# USB_Type_C.net
KiCad netlist of a schematic drawn in Altium Designer
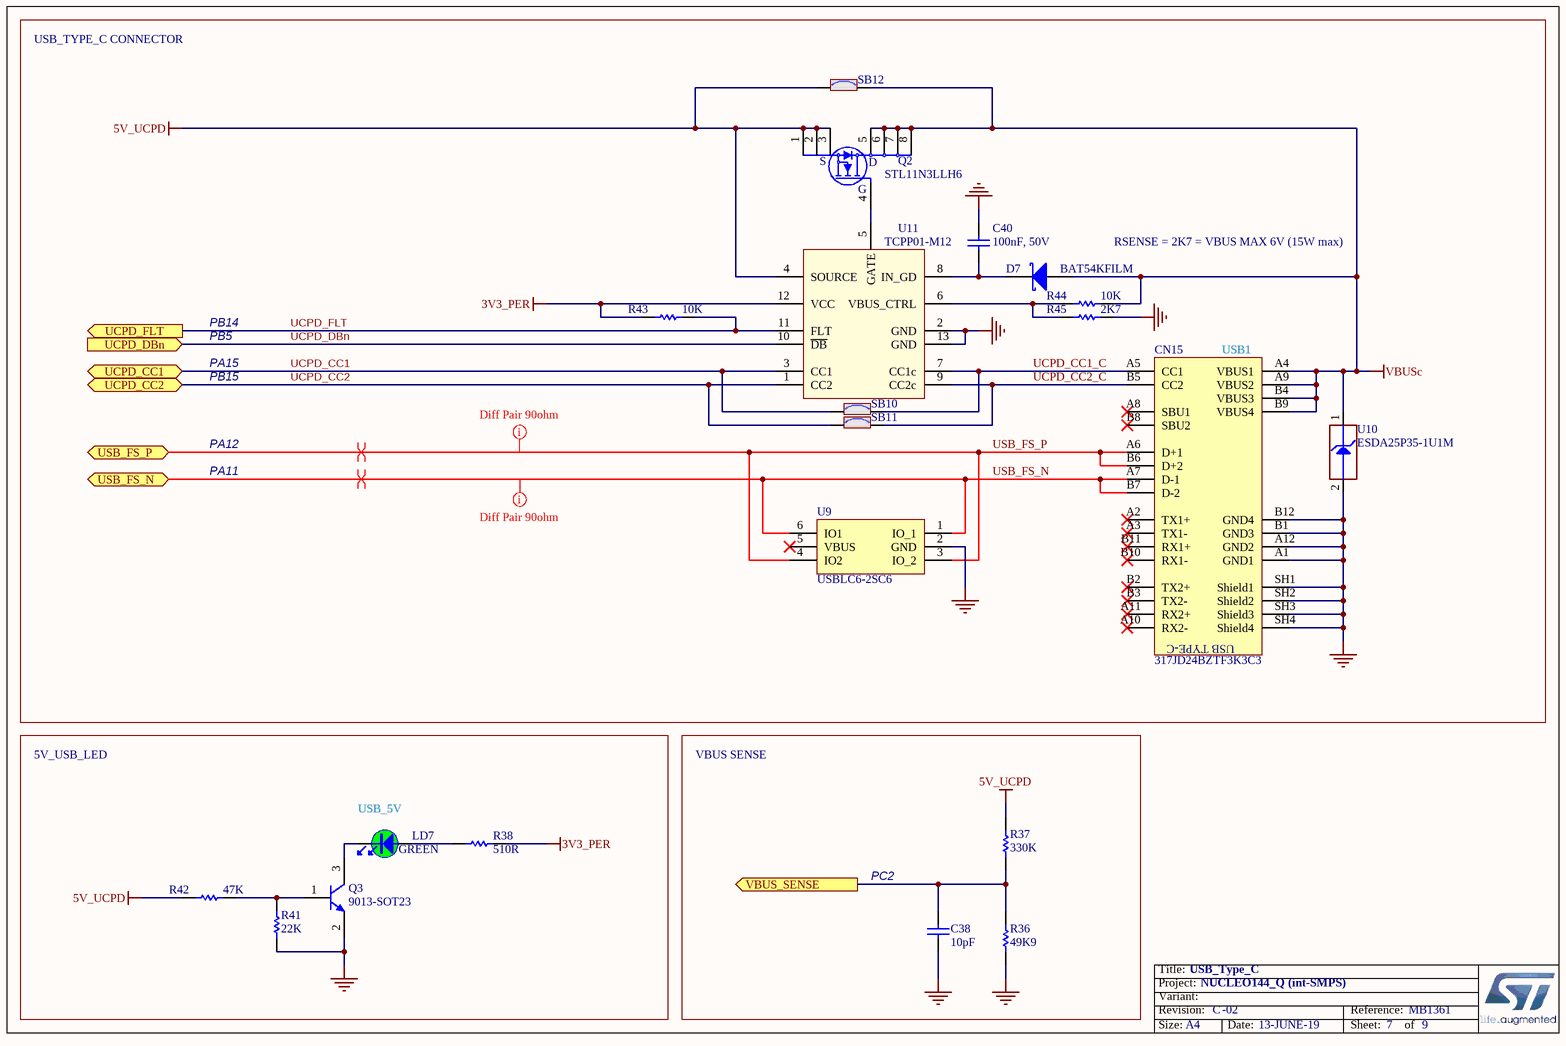
[diagram p0: USB_Type_C.SchDoc]

(export (version "E")
  (design (tool "Eeschema 10.0.6"))
  (components
    (comp (ref "C38")
      (value "10pF")
      (footprint "C0603")
      (description "Capacitor, MLCC, 10pF, 50V, NPO, 5%, 0603, T=0,8mm")
      (fields
        (field (name "INTERNAL_PART_NUMBER") "MCD-00637")
        (field (name "MANUFACTURER_PART_NUMBER") "CC0603JRNPO9BN100")
        (field (name "PROVIDED_BY") "subcon")
      )
      (libsource (lib "MCD_PARTS_database") (part "Capacitor"))
    )
    (comp (ref "C40")
      (value "100nF, 50V")
      (footprint "C0603")
      (description "Capacitor,100nF,50V,X7R,10%,0603")
      (fields
        (field (name "INTERNAL_PART_NUMBER") "MCD-01099")
        (field (name "MANUFACTURER_PART_NUMBER") "CC0603KRX7R9BB104")
        (field (name "PROVIDED_BY") "SUBCO")
      )
      (libsource (lib "MCD_PARTS_database") (part "Capacitor"))
    )
    (comp (ref "CN15")
      (value "317JD24BZTF3K3C3")
      (footprint "CON_USB-TYPEC_COXOC_317JD24BZTF3K3C3")
      (description "USB tyce C certified receptacle for 1.6mm pcb height")
      (fields
        (field (name "INTERNAL_PART_NUMBER") "MCD-01108")
        (field (name "MANUFACTURER") "CHANT SINCERE (COXOC)")
        (field (name "PROVIDED_BY") "SUBCO")
      )
      (libsource (lib "MCD_PARTS_database") (part "USB_TYPE_C_Receptacle_317JD24BZTF3K3C3"))
    )
    (comp (ref "D7")
      (value "BAT54KFILM")
      (footprint "DIO_SOD523_1A_2K")
      (description "Small signal Schottky diodes")
      (fields
        (field (name "INTERNAL_PART_NUMBER") "MCD-01677")
        (field (name "MANUFACTURER") "STMICROELECTRONICS")
        (field (name "PROVIDED_BY") "SUBCO")
      )
      (libsource (lib "MCD_PARTS_database") (part "SCHOTTKY_1A_2K"))
    )
    (comp (ref "LD7")
      (value "GREEN")
      (footprint "LED_0603_GREEN")
      (description "LED, Green, 0603")
      (fields
        (field (name "INTERNAL_PART_NUMBER") "MCD-00050")
        (field (name "MANUFACTURER_PART_NUMBER") "19-213SYGC/S530-E2/TR8")
        (field (name "PROVIDED_BY") "Subcon")
      )
      (libsource (lib "MCD_PARTS_database") (part "LED_green"))
    )
    (comp (ref "Q2")
      (value "STL11N3LLH6")
      (footprint "MOS_POWERFLAT_3P3X3P3_P065")
      (description "N-channel 30 V, 6 mΩ typ, 11 A STripFET™ H6, Power MOSFET in a PowerFLAT™ 3.3x3.3 package")
      (fields
        (field (name "INTERNAL_PART_NUMBER") "MCD-01810")
        (field (name "MANUFACTURER") "STMICROELECTRONICS")
        (field (name "PROVIDED_BY") "SUBCO with ST control")
      )
      (libsource (lib "MCD_PARTS_database") (part "STL11N3LLH6"))
    )
    (comp (ref "Q3")
      (value "9013-SOT23")
      (footprint "NPN_SOT23")
      (description "NPN Bipolar Transistor")
      (fields
        (field (name "INTERNAL_PART_NUMBER") "MCD-00073")
        (field (name "MANUFACTURER_PART_NUMBER") "BSR14")
        (field (name "PROVIDED_BY") "Subcon")
      )
      (libsource (lib "MCD_PARTS_database") (part "9013-SOT23"))
    )
    (comp (ref "R36")
      (value "49K9")
      (footprint "R0603")
      (description "Resistor,49K9,0603,1%")
      (fields
        (field (name "INTERNAL_PART_NUMBER") "MCD-01171")
        (field (name "MANUFACTURER_PART_NUMBER") "RC0603FR-0749K9L")
        (field (name "PROVIDED_BY") "Subcon")
      )
      (libsource (lib "MCD_PARTS_database") (part "Resistor"))
    )
    (comp (ref "R37")
      (value "330K")
      (footprint "R0603")
      (description "Resistor,330K,0603,1%,1/10W")
      (fields
        (field (name "INTERNAL_PART_NUMBER") "MCD-00458")
        (field (name "MANUFACTURER_PART_NUMBER") "RC0603FR-07330KL")
        (field (name "PROVIDED_BY") "Subcon")
      )
      (libsource (lib "MCD_PARTS_database") (part "Resistor"))
    )
    (comp (ref "R38")
      (value "510R")
      (footprint "R0603")
      (description "Resistor,510R,0603,1%,1/10W")
      (fields
        (field (name "INTERNAL_PART_NUMBER") "MCD-00225")
        (field (name "MANUFACTURER_PART_NUMBER") "RC0603FR-07510RL")
        (field (name "PROVIDED_BY") "Subcon")
      )
      (libsource (lib "MCD_PARTS_database") (part "Resistor"))
    )
    (comp (ref "R41")
      (value "22K")
      (footprint "R0603")
      (description "Resistor,22K,0603,1%,1/10W")
      (fields
        (field (name "INTERNAL_PART_NUMBER") "MCD-00430")
        (field (name "MANUFACTURER_PART_NUMBER") "RC0603FR-0722KL")
        (field (name "PROVIDED_BY") "Subcon")
      )
      (libsource (lib "MCD_PARTS_database") (part "Resistor"))
    )
    (comp (ref "R42")
      (value "47K")
      (footprint "R0603")
      (description "Resistor,47K,0603,1%,1/10W")
      (fields
        (field (name "INTERNAL_PART_NUMBER") "MCD-00222")
        (field (name "MANUFACTURER_PART_NUMBER") "RC0603FR-0747KL")
        (field (name "PROVIDED_BY") "Subcon")
      )
      (libsource (lib "MCD_PARTS_database") (part "Resistor"))
    )
    (comp (ref "R43")
      (value "10K")
      (footprint "R0603")
      (description "Resistor,10K,0603,1%,1/10W")
      (fields
        (field (name "INTERNAL_PART_NUMBER") "MCD-00220")
        (field (name "MANUFACTURER_PART_NUMBER") "RC0603FR-0710KL")
        (field (name "PROVIDED_BY") "SUBCO")
      )
      (libsource (lib "MCD_PARTS_database") (part "Resistor"))
    )
    (comp (ref "R44")
      (value "10K")
      (footprint "R0603")
      (description "Resistor,10K,0603,1%,1/10W")
      (fields
        (field (name "INTERNAL_PART_NUMBER") "MCD-00220")
        (field (name "MANUFACTURER_PART_NUMBER") "RC0603FR-0710KL")
        (field (name "PROVIDED_BY") "SUBCO")
      )
      (libsource (lib "MCD_PARTS_database") (part "Resistor"))
    )
    (comp (ref "R45")
      (value "2K7")
      (footprint "R0603")
      (description "Resistor,2K7,0603,1%,1/10W")
      (fields
        (field (name "INTERNAL_PART_NUMBER") "MCD-00218")
        (field (name "MANUFACTURER_PART_NUMBER") "RC0603FR-072K7L")
        (field (name "PROVIDED_BY") "SUBCO")
      )
      (libsource (lib "MCD_PARTS_database") (part "Resistor"))
    )
    (comp (ref "SB10")
      (value "~")
      (footprint "SOLDER-BRIDGE_R0603-0R")
      (description "Solder Bridge ON")
      (fields (field (name "INTERNAL_PART_NUMBER") "MCD-00071") (field (name "PROVIDED_BY") "Subcon"))
      (libsource (lib "MCD_PARTS_database") (part "SB_ON"))
    )
    (comp (ref "SB11")
      (value "~")
      (footprint "SOLDER-BRIDGE_R0603-0R")
      (description "Solder Bridge ON")
      (fields (field (name "INTERNAL_PART_NUMBER") "MCD-00071") (field (name "PROVIDED_BY") "Subcon"))
      (libsource (lib "MCD_PARTS_database") (part "SB_ON"))
    )
    (comp (ref "SB12")
      (value "~")
      (footprint "SOLDER-BRIDGE_R0603-0R")
      (description "Solder Bridge ON")
      (fields (field (name "INTERNAL_PART_NUMBER") "MCD-00071") (field (name "PROVIDED_BY") "Subcon"))
      (libsource (lib "MCD_PARTS_database") (part "SB_ON"))
    )
    (comp (ref "U9")
      (value "USBLC6-2SC6")
      (footprint "ESD_SOT23-6L")
      (description "Very low capacitance ESD protection")
      (fields
        (field (name "INTERNAL_PART_NUMBER") "MCD-00163")
        (field (name "MANUFACTURER") "STMICROELECTRONICS")
        (field (name "PROVIDED_BY") "SUBCO with ST control")
      )
      (libsource (lib "MCD_PARTS_database") (part "USBLC6-2SC6"))
    )
    (comp (ref "U10")
      (value "ESDA25P35-1U1M")
      (footprint "ESD_QFN1610_2N_1K_2A")
      (description "High power Transient voltage suppressor:25V/35A EOS and ESD transients protection.")
      (fields
        (field (name "INTERNAL_PART_NUMBER") "MCD-01207")
        (field (name "MANUFACTURER") "STMICROELECTRONICS")
        (field (name "PROVIDED_BY") "SUBCO with ST control")
      )
      (libsource (lib "MCD_PARTS_database") (part "ESD-TRANSIL"))
    )
    (comp (ref "U11")
      (value "TCPP01-M12")
      (footprint "ICC_QFN12L-EPAD_3X3_P050")
      (description "USB Type-C Port Protection for USB Power Delivery, PPS compliant")
      (fields
        (field (name "INTERNAL_PART_NUMBER") "MCD-01809")
        (field (name "MANUFACTURER") "STMICROELECTRONICS")
        (field (name "PROVIDED_BY") "SUBCO with ST control")
      )
      (libsource (lib "MCD_PARTS_database") (part "TCPP01-M12"))
    )
  )
  (nets
    (net (code "1") (name "/UCPD_CC1") (class "Default")
      (node (ref "SB10") (pin "1") (pinfunction "1_1") (pintype "passive"))
      (node (ref "U11") (pin "3") (pinfunction "CC1_3") (pintype "passive"))
    )
    (net (code "2") (name "/UCPD_CC1_C") (class "Default")
      (node (ref "CN15") (pin "A5") (pinfunction "CC1_A5") (pintype "passive"))
      (node (ref "SB10") (pin "2") (pinfunction "2_2") (pintype "passive"))
      (node (ref "U11") (pin "7") (pinfunction "CC1c_7") (pintype "passive"))
    )
    (net (code "3") (name "/UCPD_CC2") (class "Default")
      (node (ref "SB11") (pin "1") (pinfunction "1_1") (pintype "passive"))
      (node (ref "U11") (pin "1") (pinfunction "CC2_1") (pintype "passive"))
    )
    (net (code "4") (name "/UCPD_CC2_C") (class "Default")
      (node (ref "CN15") (pin "B5") (pinfunction "CC2_B5") (pintype "passive"))
      (node (ref "SB11") (pin "2") (pinfunction "2_2") (pintype "passive"))
      (node (ref "U11") (pin "9") (pinfunction "CC2c_9") (pintype "passive"))
    )
    (net (code "5") (name "/UCPD_DBn") (class "Default")
      (node (ref "U11") (pin "10") (pinfunction "~{DB}_10") (pintype "passive"))
    )
    (net (code "6") (name "/UCPD_FLT") (class "Default")
      (node (ref "R43") (pin "1") (pinfunction "1_1") (pintype "passive"))
      (node (ref "U11") (pin "11") (pinfunction "FLT_11") (pintype "passive"))
    )
    (net (code "7") (name "/USB_FS_N") (class "Default")
      (node (ref "CN15") (pin "A7") (pinfunction "D-1_A7") (pintype "passive"))
      (node (ref "CN15") (pin "B7") (pinfunction "D-2_B7") (pintype "passive"))
      (node (ref "U9") (pin "1") (pinfunction "IO_1_1") (pintype "passive"))
      (node (ref "U9") (pin "6") (pinfunction "IO1_6") (pintype "passive"))
    )
    (net (code "8") (name "/USB_FS_P") (class "Default")
      (node (ref "CN15") (pin "A6") (pinfunction "D+1_A6") (pintype "passive"))
      (node (ref "CN15") (pin "B6") (pinfunction "D+2_B6") (pintype "passive"))
      (node (ref "U9") (pin "3") (pinfunction "IO_2_3") (pintype "passive"))
      (node (ref "U9") (pin "4") (pinfunction "IO2_4") (pintype "passive"))
    )
    (net (code "9") (name "/VBUS_SENSE") (class "Default")
      (node (ref "C38") (pin "2") (pinfunction "2_2") (pintype "passive"))
      (node (ref "R36") (pin "2") (pinfunction "2_2") (pintype "passive"))
      (node (ref "R37") (pin "1") (pinfunction "1_1") (pintype "passive"))
    )
    (net (code "10") (name "3V3_PER") (class "Default")
      (node (ref "R38") (pin "1") (pinfunction "1_1") (pintype "passive"))
      (node (ref "R43") (pin "2") (pinfunction "2_2") (pintype "passive"))
      (node (ref "U11") (pin "12") (pinfunction "VCC_12") (pintype "passive"))
    )
    (net (code "11") (name "5V_UCPD") (class "Default")
      (node (ref "Q2") (pin "1") (pinfunction "S_1") (pintype "passive"))
      (node (ref "Q2") (pin "2") (pinfunction "S_2") (pintype "passive"))
      (node (ref "Q2") (pin "3") (pinfunction "S_3") (pintype "passive"))
      (node (ref "R37") (pin "2") (pinfunction "2_2") (pintype "passive"))
      (node (ref "R42") (pin "1") (pinfunction "1_1") (pintype "passive"))
      (node (ref "SB12") (pin "1") (pinfunction "1_1") (pintype "passive"))
      (node (ref "U11") (pin "4") (pinfunction "SOURCE_4") (pintype "passive"))
    )
    (net (code "12") (name "GND") (class "Default")
      (node (ref "C38") (pin "1") (pinfunction "1_1") (pintype "passive"))
      (node (ref "C40") (pin "1") (pinfunction "1_1") (pintype "passive"))
      (node (ref "CN15") (pin "A1") (pinfunction "GND1_A1") (pintype "passive"))
      (node (ref "CN15") (pin "A12") (pinfunction "GND2_A12") (pintype "passive"))
      (node (ref "CN15") (pin "B1") (pinfunction "GND3_B1") (pintype "passive"))
      (node (ref "CN15") (pin "B12") (pinfunction "GND4_B12") (pintype "passive"))
      (node (ref "CN15") (pin "SH1") (pinfunction "Shield1_SH1") (pintype "passive"))
      (node (ref "CN15") (pin "SH2") (pinfunction "Shield2_SH2") (pintype "passive"))
      (node (ref "CN15") (pin "SH3") (pinfunction "Shield3_SH3") (pintype "passive"))
      (node (ref "CN15") (pin "SH4") (pinfunction "Shield4_SH4") (pintype "passive"))
      (node (ref "Q3") (pin "2") (pinfunction "E_2") (pintype "passive"))
      (node (ref "R36") (pin "1") (pinfunction "1_1") (pintype "passive"))
      (node (ref "R41") (pin "1") (pinfunction "1_1") (pintype "passive"))
      (node (ref "R45") (pin "1") (pinfunction "1_1") (pintype "passive"))
      (node (ref "U10") (pin "2") (pinfunction "GND_2") (pintype "passive"))
      (node (ref "U11") (pin "13") (pinfunction "GND_13") (pintype "passive"))
      (node (ref "U11") (pin "2") (pinfunction "GND_2") (pintype "passive"))
      (node (ref "U9") (pin "2") (pinfunction "GND_2") (pintype "passive"))
    )
    (net (code "13") (name "Net-(D7-K)") (class "Default")
      (node (ref "C40") (pin "2") (pinfunction "2_2") (pintype "passive"))
      (node (ref "D7") (pin "2") (pinfunction "K_2") (pintype "passive"))
      (node (ref "U11") (pin "8") (pinfunction "IN_GD_8") (pintype "passive"))
    )
    (net (code "14") (name "Net-(LD7-Pad1)") (class "Default")
      (node (ref "LD7") (pin "1") (pintype "passive"))
      (node (ref "R38") (pin "2") (pinfunction "2_2") (pintype "passive"))
    )
    (net (code "15") (name "Net-(Q2-G)") (class "Default")
      (node (ref "Q2") (pin "4") (pinfunction "G_4") (pintype "passive"))
      (node (ref "U11") (pin "5") (pinfunction "GATE_5") (pintype "passive"))
    )
    (net (code "16") (name "Net-(Q3-B)") (class "Default")
      (node (ref "Q3") (pin "1") (pinfunction "B_1") (pintype "passive"))
      (node (ref "R41") (pin "2") (pinfunction "2_2") (pintype "passive"))
      (node (ref "R42") (pin "2") (pinfunction "2_2") (pintype "passive"))
    )
    (net (code "17") (name "Net-(Q3-C)") (class "Default")
      (node (ref "LD7") (pin "2") (pintype "passive"))
      (node (ref "Q3") (pin "3") (pinfunction "C_3") (pintype "passive"))
    )
    (net (code "18") (name "Net-(U11-VBUS_CTRL)") (class "Default")
      (node (ref "R44") (pin "1") (pinfunction "1_1") (pintype "passive"))
      (node (ref "R45") (pin "2") (pinfunction "2_2") (pintype "passive"))
      (node (ref "U11") (pin "6") (pinfunction "VBUS_CTRL_6") (pintype "passive"))
    )
    (net (code "19") (name "VBUSc") (class "Default")
      (node (ref "CN15") (pin "A4") (pinfunction "VBUS1_A4") (pintype "passive"))
      (node (ref "CN15") (pin "A9") (pinfunction "VBUS2_A9") (pintype "passive"))
      (node (ref "CN15") (pin "B4") (pinfunction "VBUS3_B4") (pintype "passive"))
      (node (ref "CN15") (pin "B9") (pinfunction "VBUS4_B9") (pintype "passive"))
      (node (ref "D7") (pin "1") (pinfunction "A_1") (pintype "passive"))
      (node (ref "Q2") (pin "5") (pinfunction "D_5") (pintype "passive"))
      (node (ref "Q2") (pin "6") (pinfunction "D_6") (pintype "passive"))
      (node (ref "Q2") (pin "7") (pinfunction "D_7") (pintype "passive"))
      (node (ref "Q2") (pin "8") (pinfunction "D_8") (pintype "passive"))
      (node (ref "R44") (pin "2") (pinfunction "2_2") (pintype "passive"))
      (node (ref "SB12") (pin "2") (pinfunction "2_2") (pintype "passive"))
      (node (ref "U10") (pin "1") (pinfunction "IO1_1") (pintype "passive"))
    )
    (net (code "20") (name "unconnected-(CN15-RX1+-PadB11)") (class "Default")
      (node (ref "CN15") (pin "B11") (pinfunction "RX1+_B11") (pintype "passive+no_connect"))
    )
    (net (code "21") (name "unconnected-(CN15-RX1--PadB10)") (class "Default")
      (node (ref "CN15") (pin "B10") (pinfunction "RX1-_B10") (pintype "passive+no_connect"))
    )
    (net (code "22") (name "unconnected-(CN15-RX2+-PadA11)") (class "Default")
      (node (ref "CN15") (pin "A11") (pinfunction "RX2+_A11") (pintype "passive+no_connect"))
    )
    (net (code "23") (name "unconnected-(CN15-RX2--PadA10)") (class "Default")
      (node (ref "CN15") (pin "A10") (pinfunction "RX2-_A10") (pintype "passive+no_connect"))
    )
    (net (code "24") (name "unconnected-(CN15-SBU1-PadA8)") (class "Default")
      (node (ref "CN15") (pin "A8") (pinfunction "SBU1_A8") (pintype "passive+no_connect"))
    )
    (net (code "25") (name "unconnected-(CN15-SBU2-PadB8)") (class "Default")
      (node (ref "CN15") (pin "B8") (pinfunction "SBU2_B8") (pintype "passive+no_connect"))
    )
    (net (code "26") (name "unconnected-(CN15-TX1+-PadA2)") (class "Default")
      (node (ref "CN15") (pin "A2") (pinfunction "TX1+_A2") (pintype "passive+no_connect"))
    )
    (net (code "27") (name "unconnected-(CN15-TX1--PadA3)") (class "Default")
      (node (ref "CN15") (pin "A3") (pinfunction "TX1-_A3") (pintype "passive+no_connect"))
    )
    (net (code "28") (name "unconnected-(CN15-TX2+-PadB2)") (class "Default")
      (node (ref "CN15") (pin "B2") (pinfunction "TX2+_B2") (pintype "passive+no_connect"))
    )
    (net (code "29") (name "unconnected-(CN15-TX2--PadB3)") (class "Default")
      (node (ref "CN15") (pin "B3") (pinfunction "TX2-_B3") (pintype "passive+no_connect"))
    )
    (net (code "30") (name "unconnected-(U9-VBUS-Pad5)") (class "Default")
      (node (ref "U9") (pin "5") (pinfunction "VBUS_5") (pintype "passive+no_connect"))
    )
  )
)
